# mantarray_beta2_sensor.net
KiCad netlist of a schematic drawn in Altium Designer
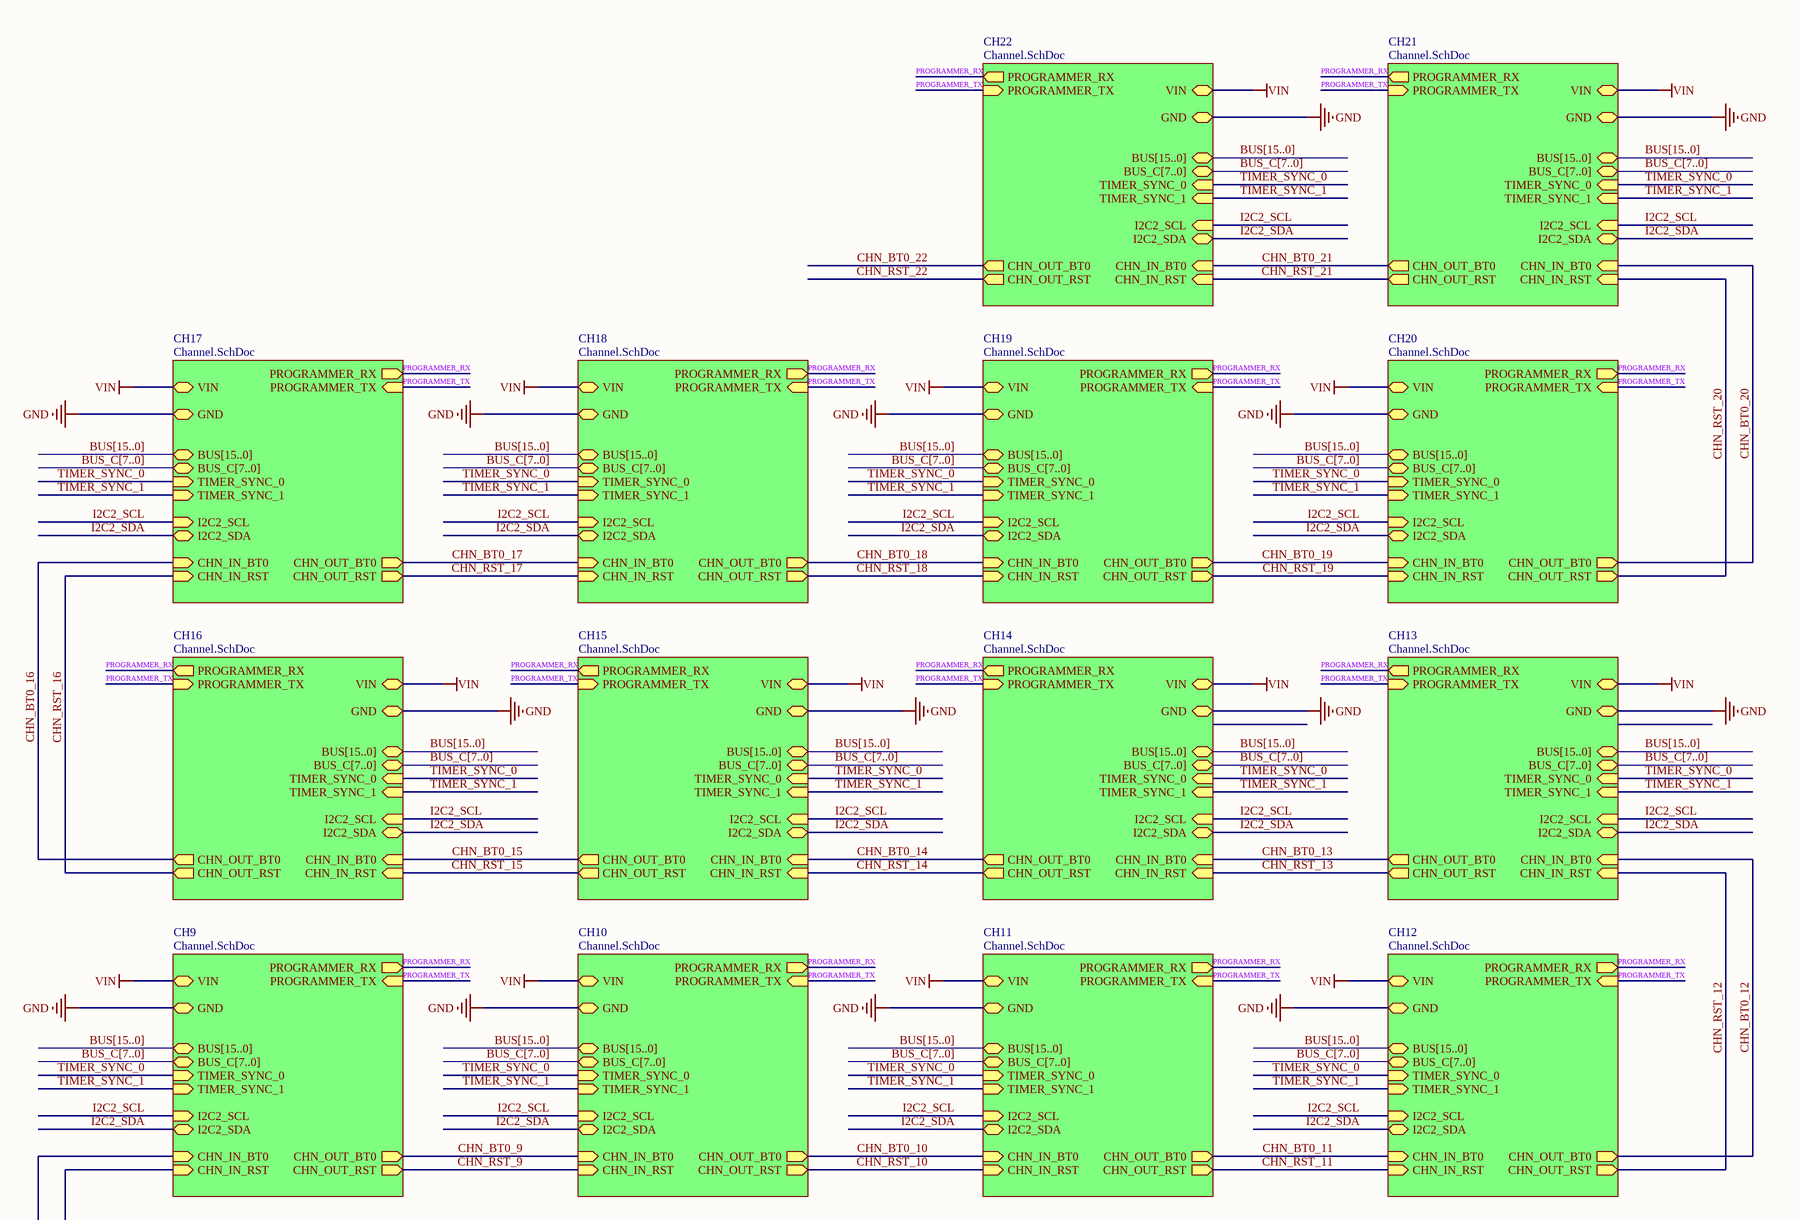
[diagram p0: mantarray_beta2_sensor.SchDoc, top right]
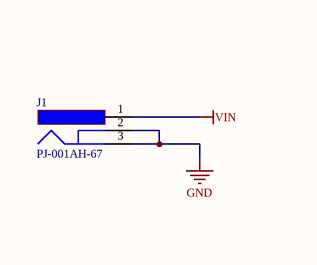
[diagram p1: mantarray_beta2_sensor.SchDoc, bottom left]
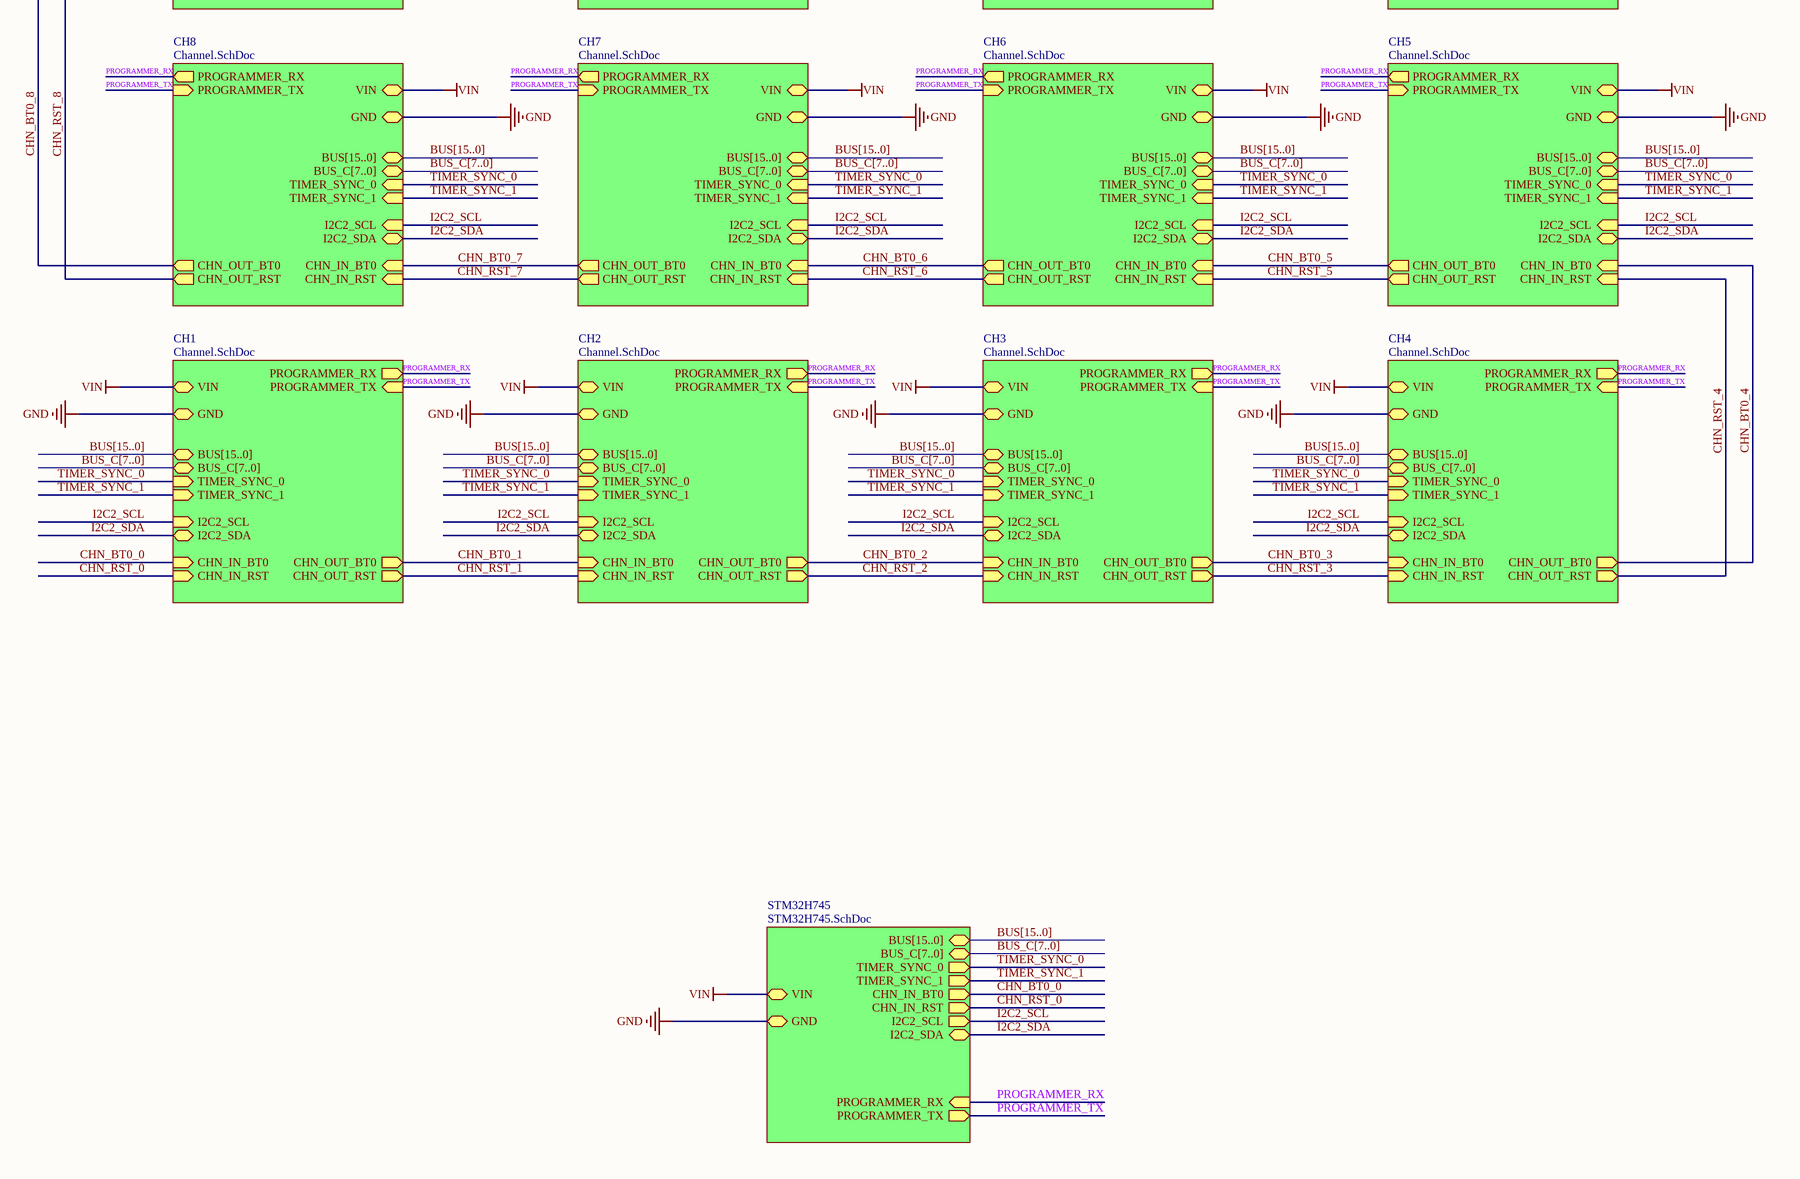
[diagram p2: mantarray_beta2_sensor.SchDoc, bottom right]

(export (version "E")
  (design (tool "Eeschema 10.0.6"))
  (components
    (comp (ref "J1")
      (value "PJ-001AH-67")
      (footprint "PJ-001AH-67")
      (description "IP67 waterproof DC Power Jack")
      (libsource (lib "mantarray_library") (part "PJ-001AH-67"))
    )
  )
  (nets
    (net (code "79") (name "GND") (class "Default")
      (node (ref "J1") (pin "2") (pinfunction "2_2") (pintype "passive"))
      (node (ref "J1") (pin "3") (pinfunction "3_3") (pintype "passive"))
    )
    (net (code "80") (name "VIN") (class "Default")
      (node (ref "J1") (pin "1") (pinfunction "1_1") (pintype "passive"))
    )
  )
)
